# 501_GridPos5.net
KiCad netlist of a schematic drawn in Altium Designer
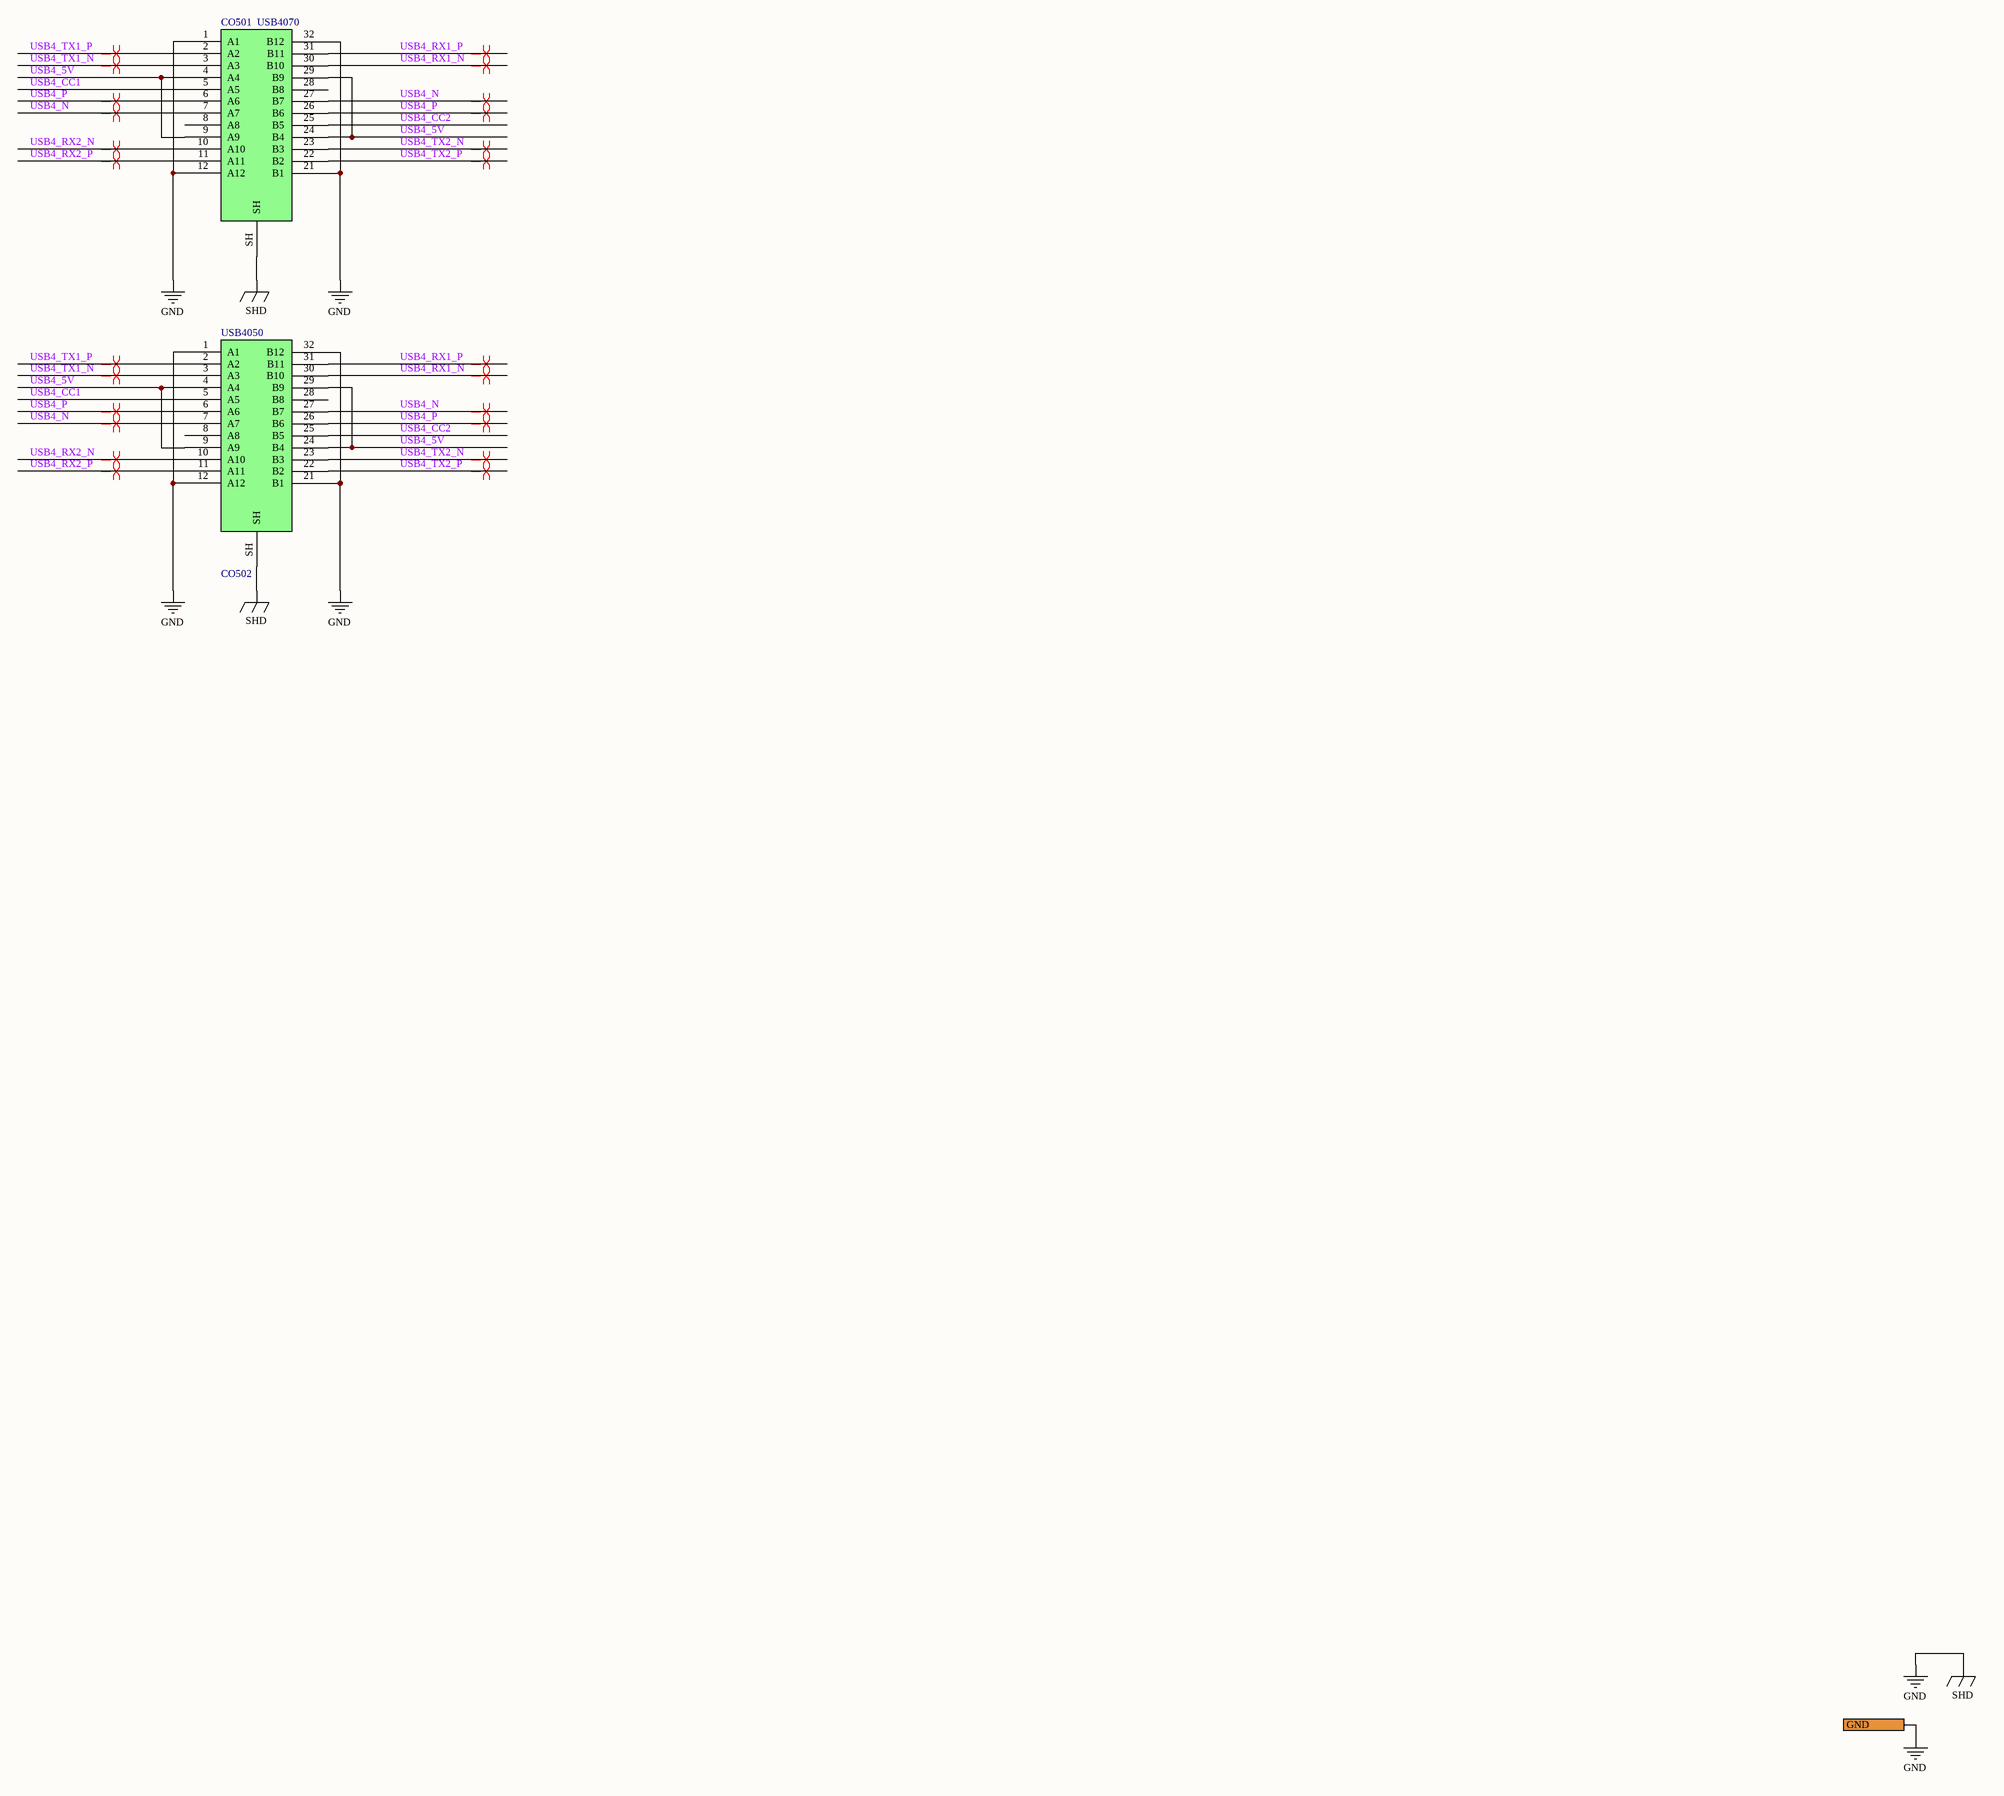
[diagram p0: 501_GridPos5.SchDoc]

(export (version "E")
  (design (tool "Eeschema 10.0.6"))
  (components
    (comp (ref "CO501")
      (value "USB4070")
      (footprint "USB4070-30-C")
      (description "USB4070-30-C")
      (fields (field (name "REFVAL") "USB4070") (field (name "PART NUMBER") "CO0021"))
      (libsource (lib "GTS_Database") (part "USB-CC"))
    )
    (comp (ref "CO502")
      (value "USB4050")
      (footprint "USB4050-30-A")
      (description "USB C connector Receptacle Horizontal")
      (fields
        (field (name "REFVAL") "USB4050")
        (field (name "PART NUMBER") "CO0039")
        (field (name "MANFACTPART") "USB4050-30-A")
      )
      (libsource (lib "") (part "USB-CC_1"))
    )
  )
  (nets
    (net (code "1") (name "/USB4_5V") (class "Default")
      (node (ref "CO501") (pin "24") (pinfunction "B4_24") (pintype "passive"))
      (node (ref "CO501") (pin "29") (pinfunction "B9_29") (pintype "passive"))
      (node (ref "CO501") (pin "4") (pinfunction "A4_4") (pintype "passive"))
      (node (ref "CO501") (pin "9") (pinfunction "A9_9") (pintype "passive"))
      (node (ref "CO502") (pin "24") (pinfunction "B4_24") (pintype "passive"))
      (node (ref "CO502") (pin "29") (pinfunction "B9_29") (pintype "passive"))
      (node (ref "CO502") (pin "4") (pinfunction "A4_4") (pintype "passive"))
      (node (ref "CO502") (pin "9") (pinfunction "A9_9") (pintype "passive"))
    )
    (net (code "2") (name "/USB4_CC1") (class "Default")
      (node (ref "CO501") (pin "5") (pinfunction "A5_5") (pintype "passive"))
      (node (ref "CO502") (pin "5") (pinfunction "A5_5") (pintype "passive"))
    )
    (net (code "3") (name "/USB4_CC2") (class "Default")
      (node (ref "CO501") (pin "25") (pinfunction "B5_25") (pintype "passive"))
      (node (ref "CO502") (pin "25") (pinfunction "B5_25") (pintype "passive"))
    )
    (net (code "4") (name "/USB4_N") (class "Default")
      (node (ref "CO501") (pin "27") (pinfunction "B7_27") (pintype "passive"))
      (node (ref "CO501") (pin "7") (pinfunction "A7_7") (pintype "passive"))
      (node (ref "CO502") (pin "27") (pinfunction "B7_27") (pintype "passive"))
      (node (ref "CO502") (pin "7") (pinfunction "A7_7") (pintype "passive"))
    )
    (net (code "5") (name "/USB4_P") (class "Default")
      (node (ref "CO501") (pin "26") (pinfunction "B6_26") (pintype "passive"))
      (node (ref "CO501") (pin "6") (pinfunction "A6_6") (pintype "passive"))
      (node (ref "CO502") (pin "26") (pinfunction "B6_26") (pintype "passive"))
      (node (ref "CO502") (pin "6") (pinfunction "A6_6") (pintype "passive"))
    )
    (net (code "6") (name "/USB4_RX1_N") (class "Default")
      (node (ref "CO501") (pin "30") (pinfunction "B10_30") (pintype "passive"))
      (node (ref "CO502") (pin "30") (pinfunction "B10_30") (pintype "passive"))
    )
    (net (code "7") (name "/USB4_RX1_P") (class "Default")
      (node (ref "CO501") (pin "31") (pinfunction "B11_31") (pintype "passive"))
      (node (ref "CO502") (pin "31") (pinfunction "B11_31") (pintype "passive"))
    )
    (net (code "8") (name "/USB4_RX2_N") (class "Default")
      (node (ref "CO501") (pin "10") (pinfunction "A10_10") (pintype "passive"))
      (node (ref "CO502") (pin "10") (pinfunction "A10_10") (pintype "passive"))
    )
    (net (code "9") (name "/USB4_RX2_P") (class "Default")
      (node (ref "CO501") (pin "11") (pinfunction "A11_11") (pintype "passive"))
      (node (ref "CO502") (pin "11") (pinfunction "A11_11") (pintype "passive"))
    )
    (net (code "10") (name "/USB4_TX1_N") (class "Default")
      (node (ref "CO501") (pin "3") (pinfunction "A3_3") (pintype "passive"))
      (node (ref "CO502") (pin "3") (pinfunction "A3_3") (pintype "passive"))
    )
    (net (code "11") (name "/USB4_TX1_P") (class "Default")
      (node (ref "CO501") (pin "2") (pinfunction "A2_2") (pintype "passive"))
      (node (ref "CO502") (pin "2") (pinfunction "A2_2") (pintype "passive"))
    )
    (net (code "12") (name "/USB4_TX2_N") (class "Default")
      (node (ref "CO501") (pin "23") (pinfunction "B3_23") (pintype "passive"))
      (node (ref "CO502") (pin "23") (pinfunction "B3_23") (pintype "passive"))
    )
    (net (code "13") (name "/USB4_TX2_P") (class "Default")
      (node (ref "CO501") (pin "22") (pinfunction "B2_22") (pintype "passive"))
      (node (ref "CO502") (pin "22") (pinfunction "B2_22") (pintype "passive"))
    )
    (net (code "14") (name "GND") (class "Default")
      (node (ref "CO501") (pin "1") (pinfunction "A1_1") (pintype "passive"))
      (node (ref "CO501") (pin "12") (pinfunction "A12_12") (pintype "passive"))
      (node (ref "CO501") (pin "21") (pinfunction "B1_21") (pintype "passive"))
      (node (ref "CO501") (pin "32") (pinfunction "B12_32") (pintype "passive"))
      (node (ref "CO501") (pin "SH") (pinfunction "SH_SH") (pintype "power_in"))
      (node (ref "CO502") (pin "1") (pinfunction "A1_1") (pintype "passive"))
      (node (ref "CO502") (pin "12") (pinfunction "A12_12") (pintype "passive"))
      (node (ref "CO502") (pin "21") (pinfunction "B1_21") (pintype "passive"))
      (node (ref "CO502") (pin "32") (pinfunction "B12_32") (pintype "passive"))
      (node (ref "CO502") (pin "SH") (pinfunction "SH_SH") (pintype "power_in"))
    )
    (net (code "15") (name "unconnected-(CO501-A8-Pad8)") (class "Default")
      (node (ref "CO501") (pin "8") (pinfunction "A8_8") (pintype "passive"))
    )
    (net (code "16") (name "unconnected-(CO501-B8-Pad28)") (class "Default")
      (node (ref "CO501") (pin "28") (pinfunction "B8_28") (pintype "passive"))
    )
    (net (code "17") (name "unconnected-(CO502-A8-Pad8)") (class "Default")
      (node (ref "CO502") (pin "8") (pinfunction "A8_8") (pintype "passive"))
    )
    (net (code "18") (name "unconnected-(CO502-B8-Pad28)") (class "Default")
      (node (ref "CO502") (pin "28") (pinfunction "B8_28") (pintype "passive"))
    )
  )
)
